# SCH_gravmaskin_sandare_2024-06-04.net
KiCad netlist of a schematic drawn in EasyEDA
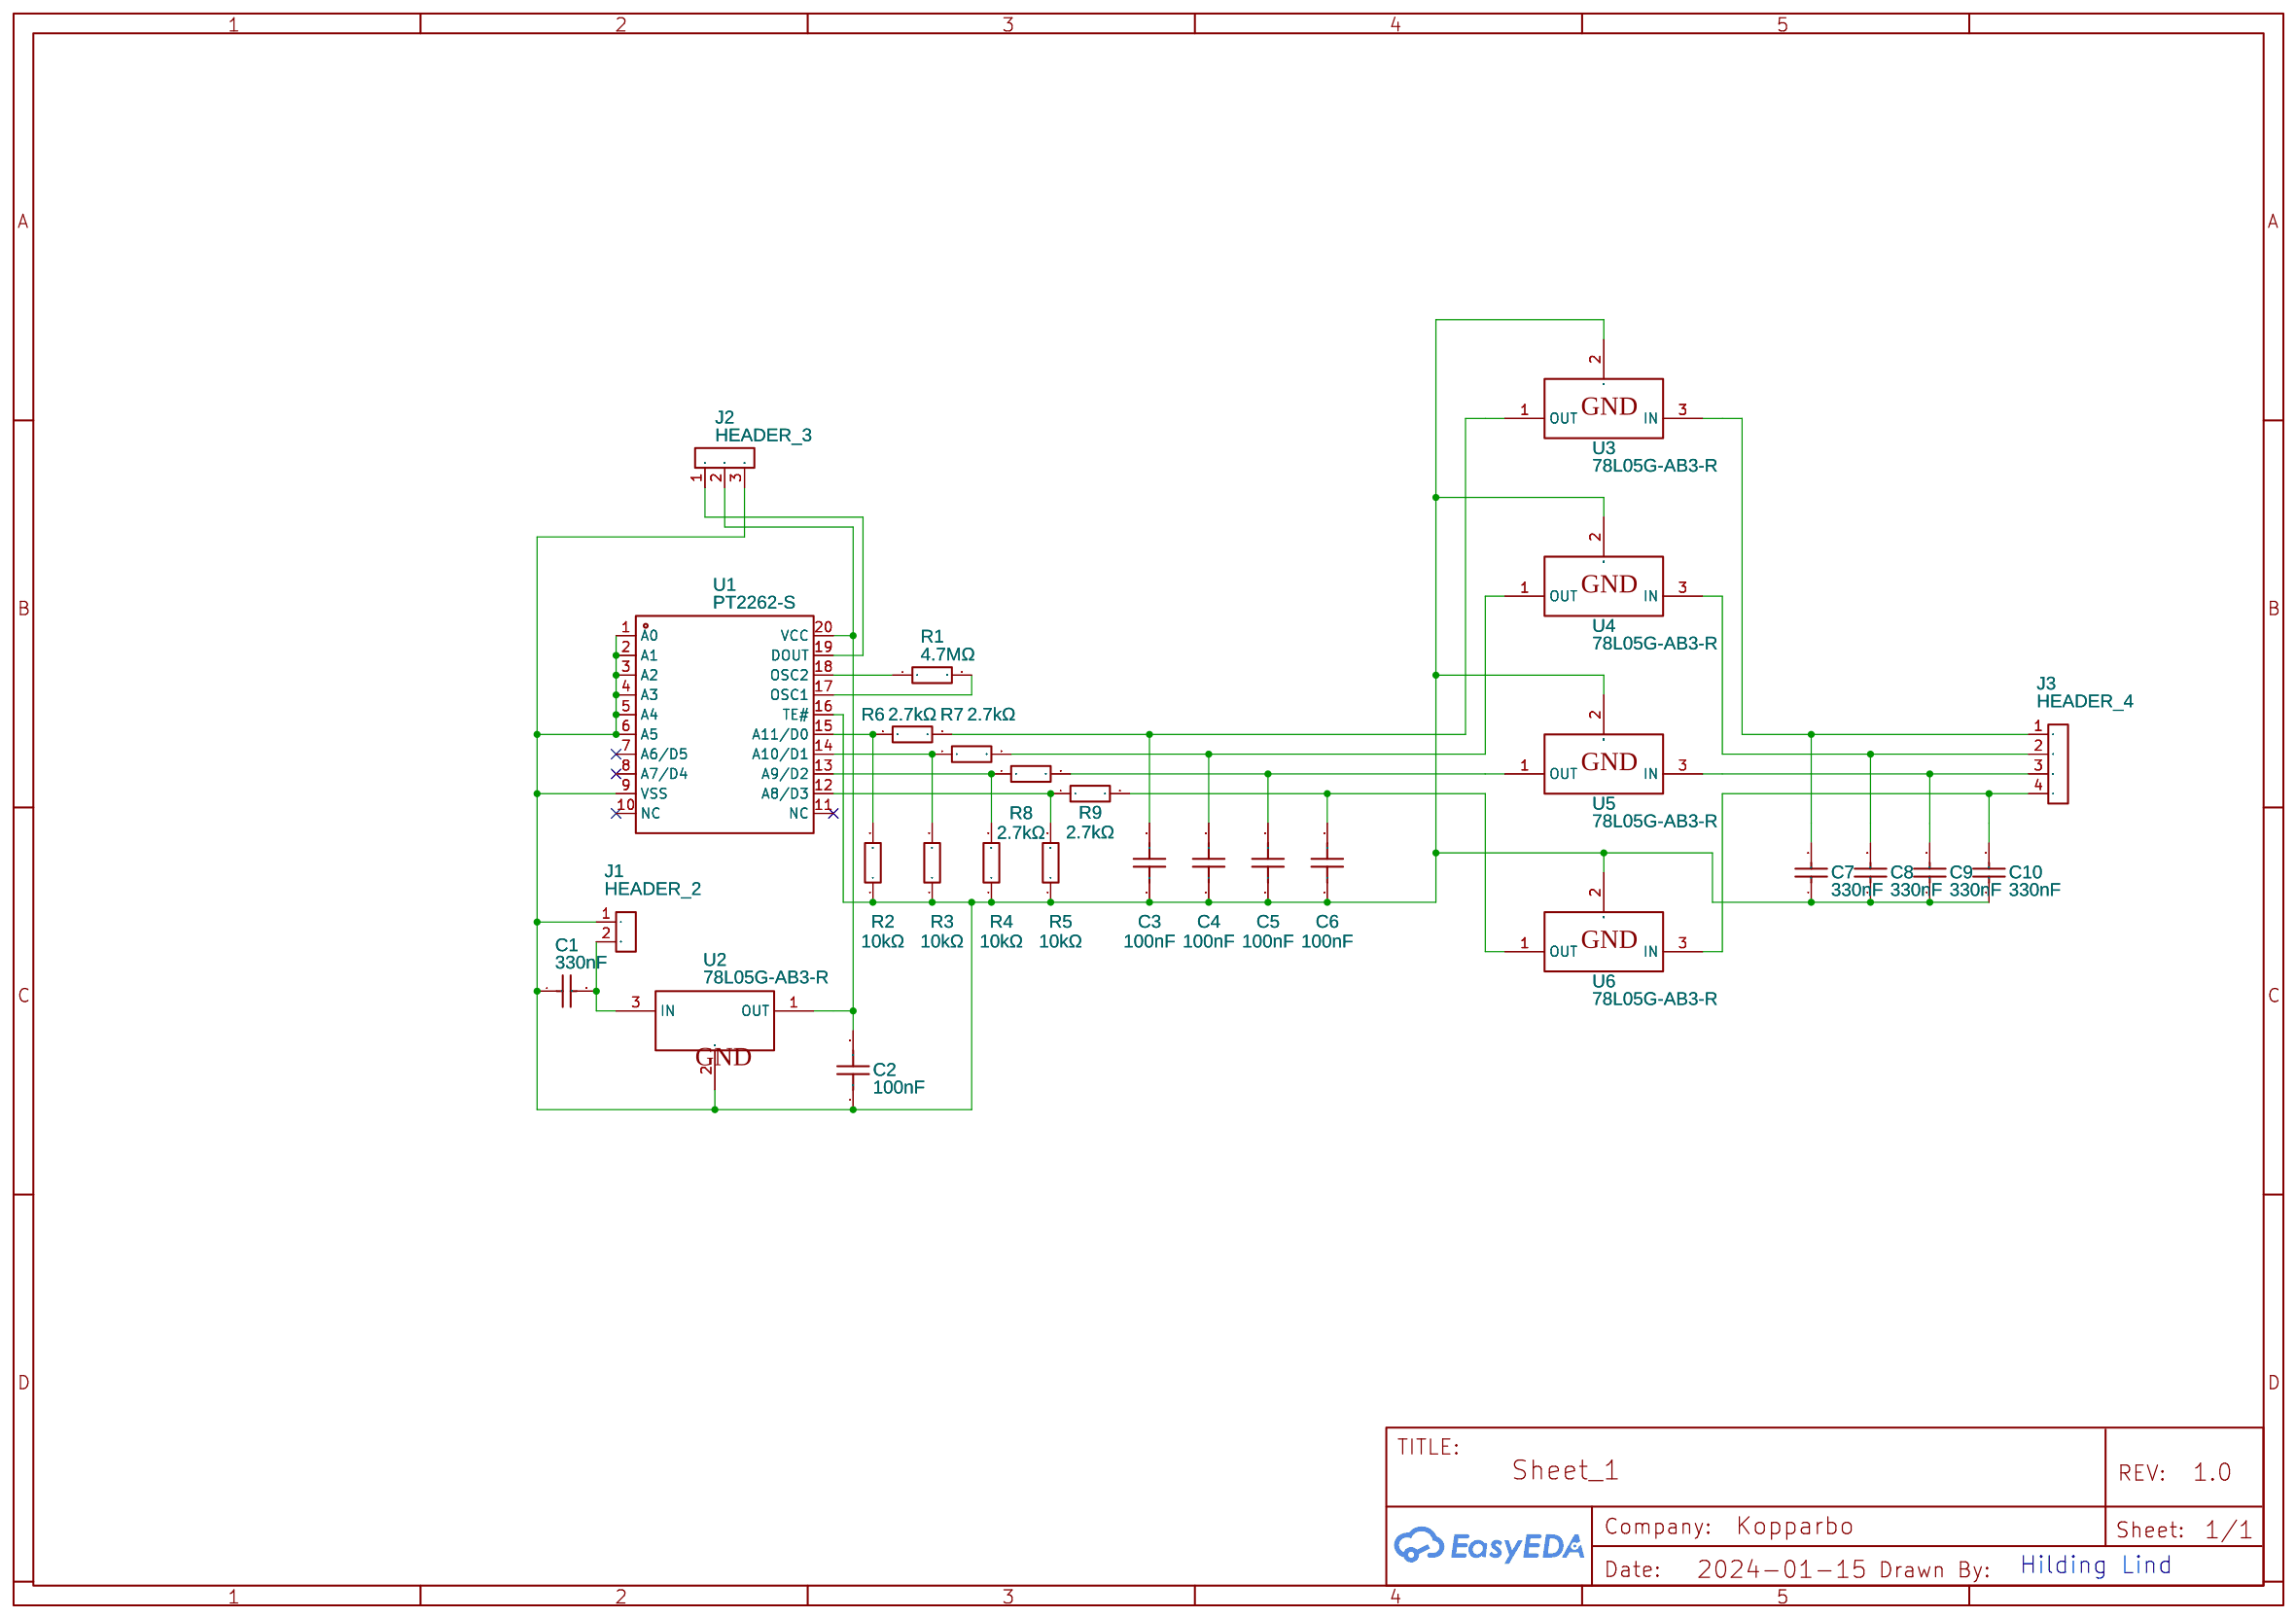
[diagram p0: schematic sheet]

(export (version "E")
  (design (tool "Eeschema 10.0.6"))
  (components
    (comp (ref "C1")
      (value "330nF")
      (fields (field (name "Manufacturer Part") "0603B334K250NT") (field (name "Manufacturer") "FH(风华)"))
      (libsource (lib "") (part "0603B334K250NT_1"))
    )
    (comp (ref "C2")
      (value "100nF")
      (fields
        (field (name "Manufacturer Part") "CC0603KRX7R9BB104")
        (field (name "Manufacturer") "YAGEO(国巨)")
      )
      (libsource (lib "") (part "CC0603KRX7R9BB104"))
    )
    (comp (ref "C3")
      (value "100nF")
      (fields
        (field (name "Manufacturer Part") "CC0603KRX7R9BB104")
        (field (name "Manufacturer") "YAGEO(国巨)")
      )
      (libsource (lib "") (part "CC0603KRX7R9BB104"))
    )
    (comp (ref "C4")
      (value "100nF")
      (fields
        (field (name "Manufacturer Part") "CC0603KRX7R9BB104")
        (field (name "Manufacturer") "YAGEO(国巨)")
      )
      (libsource (lib "") (part "CC0603KRX7R9BB104"))
    )
    (comp (ref "C5")
      (value "100nF")
      (fields
        (field (name "Manufacturer Part") "CC0603KRX7R9BB104")
        (field (name "Manufacturer") "YAGEO(国巨)")
      )
      (libsource (lib "") (part "CC0603KRX7R9BB104"))
    )
    (comp (ref "C6")
      (value "100nF")
      (fields
        (field (name "Manufacturer Part") "CC0603KRX7R9BB104")
        (field (name "Manufacturer") "YAGEO(国巨)")
      )
      (libsource (lib "") (part "CC0603KRX7R9BB104"))
    )
    (comp (ref "C7")
      (value "330nF")
      (fields (field (name "Manufacturer Part") "0603B334K250NT") (field (name "Manufacturer") "FH(风华)"))
      (libsource (lib "") (part "0603B334K250NT"))
    )
    (comp (ref "C8")
      (value "330nF")
      (fields (field (name "Manufacturer Part") "0603B334K250NT") (field (name "Manufacturer") "FH(风华)"))
      (libsource (lib "") (part "0603B334K250NT"))
    )
    (comp (ref "C9")
      (value "330nF")
      (fields (field (name "Manufacturer Part") "0603B334K250NT") (field (name "Manufacturer") "FH(风华)"))
      (libsource (lib "") (part "0603B334K250NT"))
    )
    (comp (ref "C10")
      (value "330nF")
      (fields (field (name "Manufacturer Part") "0603B334K250NT") (field (name "Manufacturer") "FH(风华)"))
      (libsource (lib "") (part "0603B334K250NT"))
    )
    (comp (ref "J1") (value "HEADER_2") (libsource (lib "") (part "HEADER_2")))
    (comp (ref "J2") (value "HEADER_3") (libsource (lib "") (part "HEADER_3")))
    (comp (ref "J3") (value "HEADER_4") (libsource (lib "") (part "HEADER_4")))
    (comp (ref "R1")
      (value "4.7MΩ")
      (fields
        (field (name "Manufacturer Part") "0603WAF4704T5E")
        (field (name "Manufacturer") "UNI-ROYAL(厚声)")
      )
      (libsource (lib "") (part "0603WAF4704T5E"))
    )
    (comp (ref "R2")
      (value "10kΩ")
      (fields
        (field (name "Manufacturer Part") "0402WGF1002TCE")
        (field (name "Manufacturer") "UNI-ROYAL(厚声)")
      )
      (libsource (lib "") (part "0402WGF1002TCE"))
    )
    (comp (ref "R3")
      (value "10kΩ")
      (fields
        (field (name "Manufacturer Part") "0402WGF1002TCE")
        (field (name "Manufacturer") "UNI-ROYAL(厚声)")
      )
      (libsource (lib "") (part "0402WGF1002TCE"))
    )
    (comp (ref "R4")
      (value "10kΩ")
      (fields
        (field (name "Manufacturer Part") "0402WGF1002TCE")
        (field (name "Manufacturer") "UNI-ROYAL(厚声)")
      )
      (libsource (lib "") (part "0402WGF1002TCE"))
    )
    (comp (ref "R5")
      (value "10kΩ")
      (fields
        (field (name "Manufacturer Part") "0402WGF1002TCE")
        (field (name "Manufacturer") "UNI-ROYAL(厚声)")
      )
      (libsource (lib "") (part "0402WGF1002TCE"))
    )
    (comp (ref "R6")
      (value "2.7kΩ")
      (fields
        (field (name "Manufacturer Part") "0603WAF2701T5E")
        (field (name "Manufacturer") "UNI-ROYAL(厚声)")
      )
      (libsource (lib "") (part "0603WAF2701T5E"))
    )
    (comp (ref "R7")
      (value "2.7kΩ")
      (fields
        (field (name "Manufacturer Part") "0603WAF2701T5E")
        (field (name "Manufacturer") "UNI-ROYAL(厚声)")
      )
      (libsource (lib "") (part "0603WAF2701T5E"))
    )
    (comp (ref "R8")
      (value "2.7kΩ")
      (fields
        (field (name "Manufacturer Part") "0603WAF2701T5E")
        (field (name "Manufacturer") "UNI-ROYAL(厚声)")
      )
      (libsource (lib "") (part "0603WAF2701T5E"))
    )
    (comp (ref "R9")
      (value "2.7kΩ")
      (fields
        (field (name "Manufacturer Part") "0603WAF2701T5E")
        (field (name "Manufacturer") "UNI-ROYAL(厚声)")
      )
      (libsource (lib "") (part "0603WAF2701T5E"))
    )
    (comp (ref "U1")
      (value "PT2262-S")
      (fields (field (name "Manufacturer") "PTC(普诚)"))
      (libsource (lib "") (part "PT2262-S"))
    )
    (comp (ref "U2")
      (value "78L05G-AB3-R")
      (fields (field (name "Manufacturer") "UTC(友顺)"))
      (libsource (lib "") (part "78L05G-AB3-R_1"))
    )
    (comp (ref "U3")
      (value "78L05G-AB3-R")
      (fields (field (name "Manufacturer") "UTC(友顺)"))
      (libsource (lib "") (part "78L05G-AB3-R"))
    )
    (comp (ref "U4")
      (value "78L05G-AB3-R")
      (fields (field (name "Manufacturer") "UTC(友顺)"))
      (libsource (lib "") (part "78L05G-AB3-R"))
    )
    (comp (ref "U5")
      (value "78L05G-AB3-R")
      (fields (field (name "Manufacturer") "UTC(友顺)"))
      (libsource (lib "") (part "78L05G-AB3-R"))
    )
    (comp (ref "U6")
      (value "78L05G-AB3-R")
      (fields (field (name "Manufacturer") "UTC(友顺)"))
      (libsource (lib "") (part "78L05G-AB3-R"))
    )
  )
  (nets
    (net (code "1") (name "Net-(U1-A0)") (class "Default")
      (node (ref "C1") (pin "1") (pinfunction "1_1") (pintype "input"))
      (node (ref "C10") (pin "1") (pinfunction "1_1") (pintype "input"))
      (node (ref "C2") (pin "1") (pinfunction "1_1") (pintype "unspecified"))
      (node (ref "C3") (pin "1") (pinfunction "1_1") (pintype "unspecified"))
      (node (ref "C4") (pin "1") (pinfunction "1_1") (pintype "unspecified"))
      (node (ref "C5") (pin "1") (pinfunction "1_1") (pintype "unspecified"))
      (node (ref "C6") (pin "1") (pinfunction "1_1") (pintype "unspecified"))
      (node (ref "C7") (pin "1") (pinfunction "1_1") (pintype "input"))
      (node (ref "C8") (pin "1") (pinfunction "1_1") (pintype "input"))
      (node (ref "C9") (pin "1") (pinfunction "1_1") (pintype "input"))
      (node (ref "J1") (pin "1") (pinfunction "1_1") (pintype "unspecified"))
      (node (ref "J2") (pin "3") (pinfunction "3_3") (pintype "unspecified"))
      (node (ref "R2") (pin "1") (pinfunction "1_1") (pintype "input"))
      (node (ref "R3") (pin "1") (pinfunction "1_1") (pintype "input"))
      (node (ref "R4") (pin "1") (pinfunction "1_1") (pintype "input"))
      (node (ref "R5") (pin "1") (pinfunction "1_1") (pintype "input"))
      (node (ref "U1") (pin "1") (pinfunction "A0_1") (pintype "unspecified"))
      (node (ref "U1") (pin "16") (pinfunction "TE#_16") (pintype "unspecified"))
      (node (ref "U1") (pin "2") (pinfunction "A1_2") (pintype "unspecified"))
      (node (ref "U1") (pin "3") (pinfunction "A2_3") (pintype "unspecified"))
      (node (ref "U1") (pin "4") (pinfunction "A3_4") (pintype "unspecified"))
      (node (ref "U1") (pin "5") (pinfunction "A4_5") (pintype "unspecified"))
      (node (ref "U1") (pin "6") (pinfunction "A5_6") (pintype "unspecified"))
      (node (ref "U1") (pin "9") (pinfunction "VSS_9") (pintype "unspecified"))
      (node (ref "U2") (pin "2") (pinfunction "GND_2") (pintype "passive"))
      (node (ref "U3") (pin "2") (pinfunction "GND_2") (pintype "passive"))
      (node (ref "U4") (pin "2") (pinfunction "GND_2") (pintype "passive"))
      (node (ref "U5") (pin "2") (pinfunction "GND_2") (pintype "passive"))
      (node (ref "U6") (pin "2") (pinfunction "GND_2") (pintype "passive"))
    )
    (net (code "2") (name "Net-(U1-A8{slash}D3)") (class "Default")
      (node (ref "R5") (pin "2") (pinfunction "2_2") (pintype "input"))
      (node (ref "R9") (pin "1") (pinfunction "1_1") (pintype "input"))
      (node (ref "U1") (pin "12") (pinfunction "A8/D3_12") (pintype "unspecified"))
    )
    (net (code "3") (name "Net-(U1-A9{slash}D2)") (class "Default")
      (node (ref "R4") (pin "2") (pinfunction "2_2") (pintype "input"))
      (node (ref "R8") (pin "1") (pinfunction "1_1") (pintype "input"))
      (node (ref "U1") (pin "13") (pinfunction "A9/D2_13") (pintype "unspecified"))
    )
    (net (code "4") (name "Net-(U1-A10{slash}D1)") (class "Default")
      (node (ref "R3") (pin "2") (pinfunction "2_2") (pintype "input"))
      (node (ref "R7") (pin "1") (pinfunction "1_1") (pintype "input"))
      (node (ref "U1") (pin "14") (pinfunction "A10/D1_14") (pintype "unspecified"))
    )
    (net (code "5") (name "Net-(U1-A11{slash}D0)") (class "Default")
      (node (ref "R2") (pin "2") (pinfunction "2_2") (pintype "input"))
      (node (ref "R6") (pin "1") (pinfunction "1_1") (pintype "input"))
      (node (ref "U1") (pin "15") (pinfunction "A11/D0_15") (pintype "unspecified"))
    )
    (net (code "6") (name "Net-(U1-DOUT)") (class "Default")
      (node (ref "J2") (pin "1") (pinfunction "1_1") (pintype "unspecified"))
      (node (ref "U1") (pin "19") (pinfunction "DOUT_19") (pintype "unspecified"))
    )
    (net (code "7") (name "Net-(U1-OSC1)") (class "Default")
      (node (ref "R1") (pin "2") (pinfunction "2_2") (pintype "input"))
      (node (ref "U1") (pin "17") (pinfunction "OSC1_17") (pintype "unspecified"))
    )
    (net (code "8") (name "Net-(U1-OSC2)") (class "Default")
      (node (ref "R1") (pin "1") (pinfunction "1_1") (pintype "input"))
      (node (ref "U1") (pin "18") (pinfunction "OSC2_18") (pintype "unspecified"))
    )
    (net (code "9") (name "Net-(U1-VCC)") (class "Default")
      (node (ref "C2") (pin "2") (pinfunction "2_2") (pintype "unspecified"))
      (node (ref "J2") (pin "2") (pinfunction "2_2") (pintype "unspecified"))
      (node (ref "U1") (pin "20") (pinfunction "VCC_20") (pintype "unspecified"))
      (node (ref "U2") (pin "1") (pinfunction "OUT_1") (pintype "passive"))
    )
    (net (code "10") (name "Net-(U2-IN)") (class "Default")
      (node (ref "C1") (pin "2") (pinfunction "2_2") (pintype "input"))
      (node (ref "J1") (pin "2") (pinfunction "2_2") (pintype "unspecified"))
      (node (ref "U2") (pin "3") (pinfunction "IN_3") (pintype "passive"))
    )
    (net (code "11") (name "Net-(U3-IN)") (class "Default")
      (node (ref "C7") (pin "2") (pinfunction "2_2") (pintype "input"))
      (node (ref "J3") (pin "1") (pinfunction "1_1") (pintype "unspecified"))
      (node (ref "U3") (pin "3") (pinfunction "IN_3") (pintype "passive"))
    )
    (net (code "12") (name "Net-(U3-OUT)") (class "Default")
      (node (ref "C3") (pin "2") (pinfunction "2_2") (pintype "unspecified"))
      (node (ref "R6") (pin "2") (pinfunction "2_2") (pintype "input"))
      (node (ref "U3") (pin "1") (pinfunction "OUT_1") (pintype "passive"))
    )
    (net (code "13") (name "Net-(U4-IN)") (class "Default")
      (node (ref "C8") (pin "2") (pinfunction "2_2") (pintype "input"))
      (node (ref "J3") (pin "2") (pinfunction "2_2") (pintype "unspecified"))
      (node (ref "U4") (pin "3") (pinfunction "IN_3") (pintype "passive"))
    )
    (net (code "14") (name "Net-(U4-OUT)") (class "Default")
      (node (ref "C4") (pin "2") (pinfunction "2_2") (pintype "unspecified"))
      (node (ref "R7") (pin "2") (pinfunction "2_2") (pintype "input"))
      (node (ref "U4") (pin "1") (pinfunction "OUT_1") (pintype "passive"))
    )
    (net (code "15") (name "Net-(U5-IN)") (class "Default")
      (node (ref "C9") (pin "2") (pinfunction "2_2") (pintype "input"))
      (node (ref "J3") (pin "3") (pinfunction "3_3") (pintype "unspecified"))
      (node (ref "U5") (pin "3") (pinfunction "IN_3") (pintype "passive"))
    )
    (net (code "16") (name "Net-(U5-OUT)") (class "Default")
      (node (ref "C5") (pin "2") (pinfunction "2_2") (pintype "unspecified"))
      (node (ref "R8") (pin "2") (pinfunction "2_2") (pintype "input"))
      (node (ref "U5") (pin "1") (pinfunction "OUT_1") (pintype "passive"))
    )
    (net (code "17") (name "Net-(U6-IN)") (class "Default")
      (node (ref "C10") (pin "2") (pinfunction "2_2") (pintype "input"))
      (node (ref "J3") (pin "4") (pinfunction "4_4") (pintype "unspecified"))
      (node (ref "U6") (pin "3") (pinfunction "IN_3") (pintype "passive"))
    )
    (net (code "18") (name "Net-(U6-OUT)") (class "Default")
      (node (ref "C6") (pin "2") (pinfunction "2_2") (pintype "unspecified"))
      (node (ref "R9") (pin "2") (pinfunction "2_2") (pintype "input"))
      (node (ref "U6") (pin "1") (pinfunction "OUT_1") (pintype "passive"))
    )
    (net (code "19") (name "unconnected-(U1-A6{slash}D5-Pad7)") (class "Default")
      (node (ref "U1") (pin "7") (pinfunction "A6/D5_7") (pintype "unspecified+no_connect"))
    )
    (net (code "20") (name "unconnected-(U1-A7{slash}D4-Pad8)") (class "Default")
      (node (ref "U1") (pin "8") (pinfunction "A7/D4_8") (pintype "unspecified+no_connect"))
    )
    (net (code "21") (name "unconnected-(U1-NC-Pad10)") (class "Default")
      (node (ref "U1") (pin "10") (pinfunction "NC_10") (pintype "unspecified+no_connect"))
    )
    (net (code "22") (name "unconnected-(U1-NC-Pad11)") (class "Default")
      (node (ref "U1") (pin "11") (pinfunction "NC_11") (pintype "unspecified+no_connect"))
    )
  )
)
